# Sheet2.net
KiCad netlist of a schematic drawn in Altium Designer
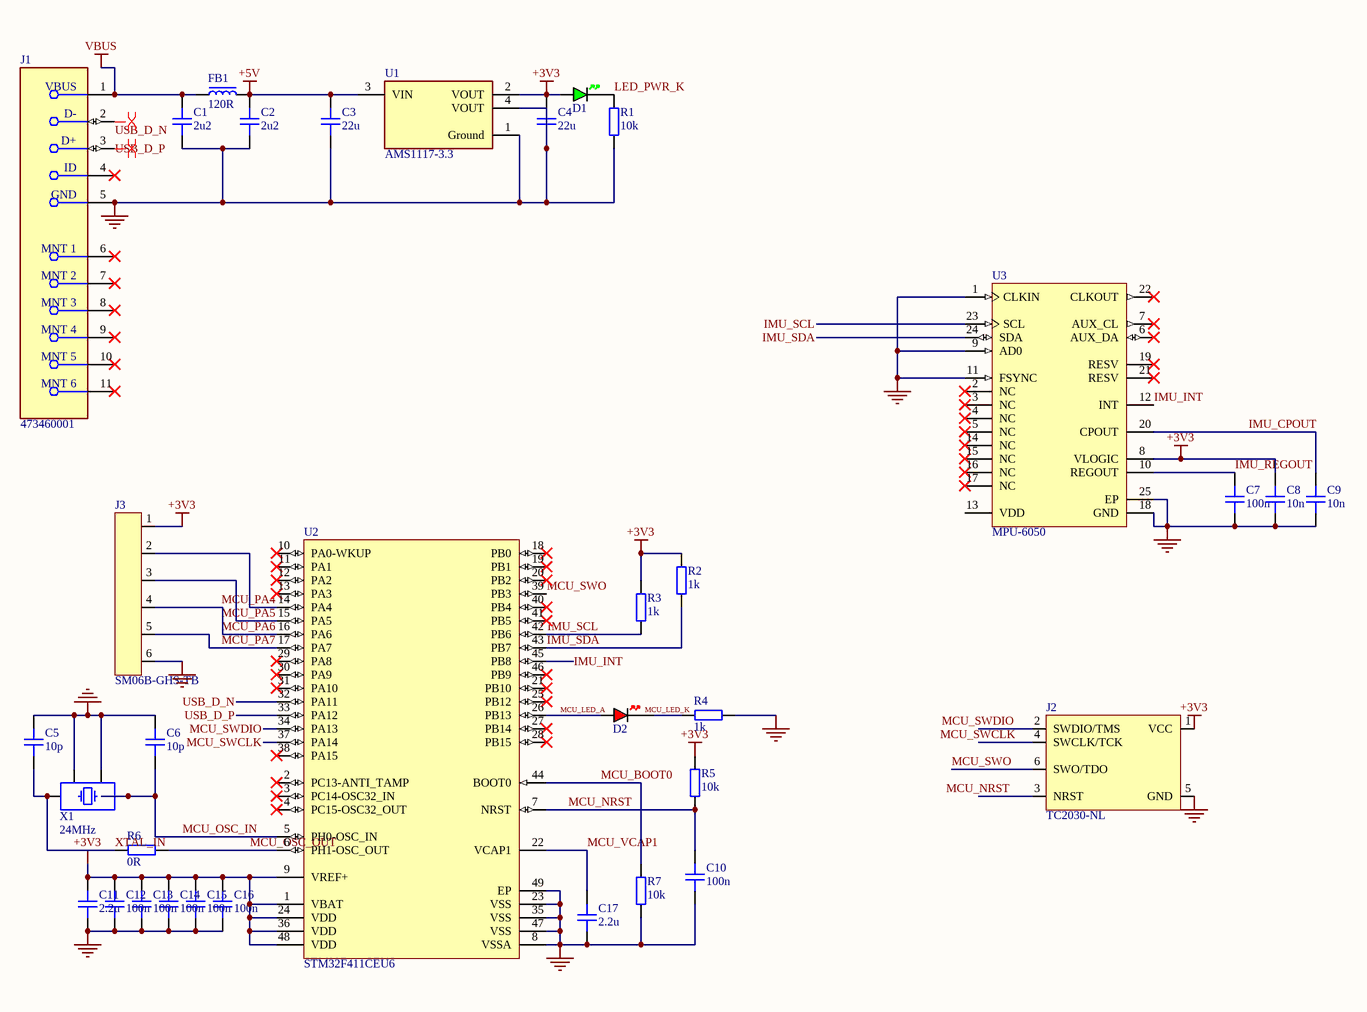
[diagram p0: Sheet2.SchDoc]

(export (version "E")
  (design (tool "Eeschema 10.0.6"))
  (components
    (comp (ref "C1")
      (value "2u2")
      (footprint "CAP_0402")
      (description "Capacitor SMD 0402")
      (libsource (lib "Schematic-Lib-PhilsLab") (part "CAP_0402"))
    )
    (comp (ref "C2")
      (value "2u2")
      (footprint "CAP_0402")
      (description "Capacitor SMD 0402")
      (libsource (lib "Schematic-Lib-PhilsLab") (part "CAP_0402"))
    )
    (comp (ref "C3")
      (value "22u")
      (footprint "CAP_0805")
      (description "Capacitor SMD 0805")
      (libsource (lib "Schematic-Lib-PhilsLab") (part "CAP_0805"))
    )
    (comp (ref "C4")
      (value "22u")
      (footprint "CAP_0805")
      (description "Capacitor SMD 0805")
      (libsource (lib "Schematic-Lib-PhilsLab") (part "CAP_0805"))
    )
    (comp (ref "C5")
      (value "10p")
      (footprint "CAP_0402")
      (description "Capacitor SMD 0402")
      (libsource (lib "Schematic-Lib-PhilsLab") (part "CAP_0402"))
    )
    (comp (ref "C6")
      (value "10p")
      (footprint "CAP_0402")
      (description "Capacitor SMD 0402")
      (libsource (lib "Schematic-Lib-PhilsLab") (part "CAP_0402"))
    )
    (comp (ref "C7")
      (value "100n")
      (footprint "CAP_0402")
      (description "Capacitor SMD 0402")
      (libsource (lib "Schematic-Lib-PhilsLab") (part "CAP_0402"))
    )
    (comp (ref "C8")
      (value "10n")
      (footprint "CAP_0402")
      (description "Capacitor SMD 0402")
      (libsource (lib "Schematic-Lib-PhilsLab") (part "CAP_0402"))
    )
    (comp (ref "C9")
      (value "10n")
      (footprint "CAP_0402")
      (description "Capacitor SMD 0402")
      (libsource (lib "Schematic-Lib-PhilsLab") (part "CAP_0402"))
    )
    (comp (ref "C10")
      (value "100n")
      (footprint "CAP_0402")
      (description "Capacitor SMD 0402")
      (libsource (lib "Schematic-Lib-PhilsLab") (part "CAP_0402"))
    )
    (comp (ref "C11")
      (value "2.2u")
      (footprint "CAP_0603")
      (description "Capacitor SMD 0603")
      (libsource (lib "Schematic-Lib-PhilsLab") (part "CAP_0603"))
    )
    (comp (ref "C12")
      (value "100n")
      (footprint "CAP_0402")
      (description "Capacitor SMD 0402")
      (libsource (lib "Schematic-Lib-PhilsLab") (part "CAP_0402"))
    )
    (comp (ref "C13")
      (value "100n")
      (footprint "CAP_0402")
      (description "Capacitor SMD 0402")
      (libsource (lib "Schematic-Lib-PhilsLab") (part "CAP_0402"))
    )
    (comp (ref "C14")
      (value "100n")
      (footprint "CAP_0402")
      (description "Capacitor SMD 0402")
      (libsource (lib "Schematic-Lib-PhilsLab") (part "CAP_0402"))
    )
    (comp (ref "C15")
      (value "100n")
      (footprint "CAP_0402")
      (description "Capacitor SMD 0402")
      (libsource (lib "Schematic-Lib-PhilsLab") (part "CAP_0402"))
    )
    (comp (ref "C16")
      (value "100n")
      (footprint "CAP_0402")
      (description "Capacitor SMD 0402")
      (libsource (lib "Schematic-Lib-PhilsLab") (part "CAP_0402"))
    )
    (comp (ref "C17")
      (value "2.2u")
      (footprint "CAP_0603")
      (description "Capacitor SMD 0603")
      (libsource (lib "Schematic-Lib-PhilsLab") (part "CAP_0603"))
    )
    (comp (ref "D1")
      (value "GREEN")
      (footprint "LED_0402_GREEN")
      (description "LED 0402 GREEN SMD")
      (libsource (lib "Schematic-Lib-PhilsLab") (part "LED_0402_GREEN"))
    )
    (comp (ref "D2")
      (value "RED")
      (footprint "LED_0402_RED")
      (description "LED 0402 RED SMD")
      (libsource (lib "Schematic-Lib-PhilsLab") (part "LED_0402_RED"))
    )
    (comp (ref "FB1")
      (value "120R")
      (footprint "FB_0603")
      (description "Ferrite Bead SMD 0603")
      (libsource (lib "Schematic-Lib-PhilsLab") (part "FB_0603"))
    )
    (comp (ref "J1")
      (value "473460001")
      (footprint "FP-473460001-MFG")
      (description "USB - micro B USB 2.0 Receptacle Connector 5 Position Surface Mount, Right Angle")
      (fields (field (name "OCTOPART") "https://octopart.com/47346-0001-molex-7164928"))
      (libsource (lib "Altium Content Vault") (part "53ae1f1d9b557310b43ca686e5bb76a"))
    )
    (comp (ref "J2")
      (value "TC2030-NL")
      (footprint "TC2030-NL-FP")
      (description "Tag-Connect No-Solder SWD Debug Connector (No Legs) DO NOT PLACE")
      (fields
        (field (name "MANUFACTURER") "Tag-Connect")
        (field (name "MANUFACTURER PART NUMBER") "TC2030-NL-FP")
      )
      (libsource (lib "Schematic-Lib-PhilsLab") (part "TC2030-NL"))
    )
    (comp (ref "J3")
      (value "SM06B-GHS-TB")
      (footprint "SM06B-GHS-TB")
      (description "Header Connector 6 Position 1.25MM Pitch SMD Horizontal JST GH")
      (fields (field (name "MANUFACTURER") "JST"))
      (libsource (lib "Schematic-Lib-PhilsLab") (part "SM06B-GHS-TB"))
    )
    (comp (ref "R1")
      (value "10k")
      (footprint "RES_0402")
      (description "Resistor SMD 0402")
      (libsource (lib "Schematic-Lib-PhilsLab") (part "RES_0402"))
    )
    (comp (ref "R2")
      (value "1k")
      (footprint "RES_0402")
      (description "Resistor SMD 0402")
      (libsource (lib "Schematic-Lib-PhilsLab") (part "RES_0402"))
    )
    (comp (ref "R3")
      (value "1k")
      (footprint "RES_0402")
      (description "Resistor SMD 0402")
      (libsource (lib "Schematic-Lib-PhilsLab") (part "RES_0402"))
    )
    (comp (ref "R4")
      (value "1k")
      (footprint "RES_0402")
      (description "Resistor SMD 0402")
      (libsource (lib "Schematic-Lib-PhilsLab") (part "RES_0402"))
    )
    (comp (ref "R5")
      (value "10k")
      (footprint "RES_0402")
      (description "Resistor SMD 0402")
      (libsource (lib "Schematic-Lib-PhilsLab") (part "RES_0402"))
    )
    (comp (ref "R6")
      (value "0R")
      (footprint "RES_0402")
      (description "Resistor SMD 0402")
      (libsource (lib "Schematic-Lib-PhilsLab") (part "RES_0402"))
    )
    (comp (ref "R7")
      (value "10k")
      (footprint "RES_0402")
      (description "Resistor SMD 0402")
      (libsource (lib "Schematic-Lib-PhilsLab") (part "RES_0402"))
    )
    (comp (ref "U1")
      (value "AMS1117-3.3")
      (footprint "FP-AMS1117-IPC_C")
      (description "LDO Voltage Regulators 1A, 3.3V")
      (fields
        (field (name "OCTOPART") "https://octopart.com/ams1117-3.3-advanced+monolithic+systems-25899300")
        (field (name "MANUFACTURER") "Advanced Monolithic Systems")
      )
      (libsource (lib "Altium Content Vault") (part "8bdbb5f8e77002000e30dd2845d0354"))
    )
    (comp (ref "U2")
      (value "STM32F411CEU6")
      (footprint "STM-UFQFPN48_L")
      (libsource (lib "Altium Content Vault") (part "MC-ARM-STM32F411-UFQFPN48"))
    )
    (comp (ref "U3")
      (value "MPU-6050")
      (footprint "IS-QFN-24_V")
      (fields (field (name "MANUFACTURER") "InvenSense"))
      (libsource (lib "Altium Content Vault") (part "IS-MPU-6050-QFN-24"))
    )
    (comp (ref "X1")
      (value "24MHz")
      (footprint "XTAL_3225")
      (description "Crystal SMD 24MHz 10PPM 7pF 3225")
      (fields
        (field (name "MANUFACTURER") "Epson")
        (field (name "MANUFACTURER PART NUMBER") "TSX-3225 24.0000MF15X-AC")
      )
      (libsource (lib "Schematic-Lib-PhilsLab") (part "TSX-3225_24.0000MF15X-AC"))
    )
  )
  (nets
    (net (code "1") (name "+3V3") (class "Default")
      (node (ref "C11") (pin "2") (pinfunction "2_2") (pintype "passive"))
      (node (ref "C12") (pin "2") (pinfunction "2_2") (pintype "passive"))
      (node (ref "C13") (pin "2") (pinfunction "2_2") (pintype "passive"))
      (node (ref "C14") (pin "2") (pinfunction "2_2") (pintype "passive"))
      (node (ref "C15") (pin "2") (pinfunction "2_2") (pintype "passive"))
      (node (ref "C16") (pin "2") (pinfunction "2_2") (pintype "passive"))
      (node (ref "C4") (pin "2") (pinfunction "2_2") (pintype "passive"))
      (node (ref "C8") (pin "2") (pinfunction "2_2") (pintype "passive"))
      (node (ref "D1") (pin "A") (pinfunction "A_A") (pintype "passive"))
      (node (ref "J2") (pin "1") (pinfunction "VCC_1") (pintype "passive"))
      (node (ref "J3") (pin "1") (pinfunction "1_1") (pintype "passive"))
      (node (ref "R2") (pin "1") (pinfunction "1_1") (pintype "passive"))
      (node (ref "R3") (pin "1") (pinfunction "1_1") (pintype "passive"))
      (node (ref "R5") (pin "2") (pinfunction "2_2") (pintype "passive"))
      (node (ref "U1") (pin "2") (pinfunction "VOUT_2") (pintype "passive"))
      (node (ref "U2") (pin "1") (pinfunction "VBAT_1") (pintype "power_in"))
      (node (ref "U2") (pin "24") (pinfunction "VDD_24") (pintype "power_in"))
      (node (ref "U2") (pin "36") (pinfunction "VDD_36") (pintype "power_in"))
      (node (ref "U2") (pin "48") (pinfunction "VDD_48") (pintype "power_in"))
      (node (ref "U2") (pin "9") (pinfunction "VREF+_9") (pintype "power_in"))
      (node (ref "U3") (pin "8") (pinfunction "VLOGIC_8") (pintype "power_in"))
    )
    (net (code "2") (name "+5V") (class "Default")
      (node (ref "C2") (pin "2") (pinfunction "2_2") (pintype "passive"))
      (node (ref "C3") (pin "2") (pinfunction "2_2") (pintype "passive"))
      (node (ref "FB1") (pin "2") (pinfunction "2_2") (pintype "passive"))
      (node (ref "U1") (pin "3") (pinfunction "VIN_3") (pintype "power_in"))
    )
    (net (code "3") (name "/IMU_CPOUT") (class "Default")
      (node (ref "C9") (pin "2") (pinfunction "2_2") (pintype "passive"))
      (node (ref "U3") (pin "20") (pinfunction "CPOUT_20") (pintype "passive"))
    )
    (net (code "4") (name "/IMU_INT") (class "Default")
      (node (ref "U2") (pin "45") (pinfunction "PB8_45") (pintype "bidirectional"))
      (node (ref "U3") (pin "12") (pinfunction "INT_12") (pintype "open_collector"))
    )
    (net (code "5") (name "/IMU_REGOUT") (class "Default")
      (node (ref "C7") (pin "2") (pinfunction "2_2") (pintype "passive"))
      (node (ref "U3") (pin "10") (pinfunction "REGOUT_10") (pintype "passive"))
    )
    (net (code "6") (name "/IMU_SCL") (class "Default")
      (node (ref "R3") (pin "2") (pinfunction "2_2") (pintype "passive"))
      (node (ref "U2") (pin "42") (pinfunction "PB6_42") (pintype "bidirectional"))
      (node (ref "U3") (pin "23") (pinfunction "SCL_23") (pintype "input"))
    )
    (net (code "7") (name "/IMU_SDA") (class "Default")
      (node (ref "R2") (pin "2") (pinfunction "2_2") (pintype "passive"))
      (node (ref "U2") (pin "43") (pinfunction "PB7_43") (pintype "bidirectional"))
      (node (ref "U3") (pin "24") (pinfunction "SDA_24") (pintype "bidirectional"))
    )
    (net (code "8") (name "/LED_PWR_K") (class "Default")
      (node (ref "D1") (pin "K") (pinfunction "K_K") (pintype "passive"))
      (node (ref "R1") (pin "2") (pinfunction "2_2") (pintype "passive"))
    )
    (net (code "9") (name "/MCU_BOOT0") (class "Default")
      (node (ref "R7") (pin "2") (pinfunction "2_2") (pintype "passive"))
      (node (ref "U2") (pin "44") (pinfunction "BOOT0_44") (pintype "input"))
    )
    (net (code "10") (name "/MCU_LED_A") (class "Default")
      (node (ref "D2") (pin "A") (pinfunction "A_A") (pintype "passive"))
      (node (ref "U2") (pin "26") (pinfunction "PB13_26") (pintype "bidirectional"))
    )
    (net (code "11") (name "/MCU_LED_K") (class "Default")
      (node (ref "D2") (pin "K") (pinfunction "K_K") (pintype "passive"))
      (node (ref "R4") (pin "2") (pinfunction "2_2") (pintype "passive"))
    )
    (net (code "12") (name "/MCU_NRST") (class "Default")
      (node (ref "C10") (pin "2") (pinfunction "2_2") (pintype "passive"))
      (node (ref "J2") (pin "3") (pinfunction "NRST_3") (pintype "passive"))
      (node (ref "R5") (pin "1") (pinfunction "1_1") (pintype "passive"))
      (node (ref "U2") (pin "7") (pinfunction "NRST_7") (pintype "bidirectional"))
    )
    (net (code "13") (name "/MCU_OSC_IN") (class "Default")
      (node (ref "C6") (pin "1") (pinfunction "1_1") (pintype "passive"))
      (node (ref "U2") (pin "5") (pinfunction "PH0-OSC_IN_5") (pintype "bidirectional"))
      (node (ref "X1") (pin "1") (pinfunction "1_1") (pintype "passive"))
    )
    (net (code "14") (name "/MCU_OSC_OUT") (class "Default")
      (node (ref "R6") (pin "1") (pinfunction "1_1") (pintype "passive"))
      (node (ref "U2") (pin "6") (pinfunction "PH1-OSC_OUT_6") (pintype "bidirectional"))
    )
    (net (code "15") (name "/MCU_PA4") (class "Default")
      (node (ref "J3") (pin "2") (pinfunction "2_2") (pintype "passive"))
      (node (ref "U2") (pin "14") (pinfunction "PA4_14") (pintype "bidirectional"))
    )
    (net (code "16") (name "/MCU_PA5") (class "Default")
      (node (ref "J3") (pin "3") (pinfunction "3_3") (pintype "passive"))
      (node (ref "U2") (pin "15") (pinfunction "PA5_15") (pintype "bidirectional"))
    )
    (net (code "17") (name "/MCU_PA6") (class "Default")
      (node (ref "J3") (pin "4") (pinfunction "4_4") (pintype "passive"))
      (node (ref "U2") (pin "16") (pinfunction "PA6_16") (pintype "bidirectional"))
    )
    (net (code "18") (name "/MCU_PA7") (class "Default")
      (node (ref "J3") (pin "5") (pinfunction "5_5") (pintype "passive"))
      (node (ref "U2") (pin "17") (pinfunction "PA7_17") (pintype "bidirectional"))
    )
    (net (code "19") (name "/MCU_SWCLK") (class "Default")
      (node (ref "J2") (pin "4") (pinfunction "SWCLK/TCK_4") (pintype "passive"))
      (node (ref "U2") (pin "37") (pinfunction "PA14_37") (pintype "bidirectional"))
    )
    (net (code "20") (name "/MCU_SWDIO") (class "Default")
      (node (ref "J2") (pin "2") (pinfunction "SWDIO/TMS_2") (pintype "passive"))
      (node (ref "U2") (pin "34") (pinfunction "PA13_34") (pintype "bidirectional"))
    )
    (net (code "21") (name "/MCU_SWO") (class "Default")
      (node (ref "J2") (pin "6") (pinfunction "SWO/TDO_6") (pintype "passive"))
      (node (ref "U2") (pin "39") (pinfunction "PB3_39") (pintype "bidirectional"))
    )
    (net (code "22") (name "/MCU_VCAP1") (class "Default")
      (node (ref "C17") (pin "2") (pinfunction "2_2") (pintype "passive"))
      (node (ref "U2") (pin "22") (pinfunction "VCAP1_22") (pintype "passive"))
    )
    (net (code "23") (name "/USB_D_N") (class "Default")
      (node (ref "J1") (pin "2") (pinfunction "D-_2") (pintype "bidirectional"))
      (node (ref "U2") (pin "32") (pinfunction "PA11_32") (pintype "bidirectional"))
    )
    (net (code "24") (name "/USB_D_P") (class "Default")
      (node (ref "J1") (pin "3") (pinfunction "D+_3") (pintype "bidirectional"))
      (node (ref "U2") (pin "33") (pinfunction "PA12_33") (pintype "bidirectional"))
    )
    (net (code "25") (name "/XTAL_IN") (class "Default")
      (node (ref "C5") (pin "1") (pinfunction "1_1") (pintype "passive"))
      (node (ref "R6") (pin "2") (pinfunction "2_2") (pintype "passive"))
      (node (ref "X1") (pin "3") (pinfunction "3_3") (pintype "passive"))
    )
    (net (code "26") (name "GND") (class "Default")
      (node (ref "C1") (pin "1") (pinfunction "1_1") (pintype "passive"))
      (node (ref "C10") (pin "1") (pinfunction "1_1") (pintype "passive"))
      (node (ref "C11") (pin "1") (pinfunction "1_1") (pintype "passive"))
      (node (ref "C12") (pin "1") (pinfunction "1_1") (pintype "passive"))
      (node (ref "C13") (pin "1") (pinfunction "1_1") (pintype "passive"))
      (node (ref "C14") (pin "1") (pinfunction "1_1") (pintype "passive"))
      (node (ref "C15") (pin "1") (pinfunction "1_1") (pintype "passive"))
      (node (ref "C16") (pin "1") (pinfunction "1_1") (pintype "passive"))
      (node (ref "C17") (pin "1") (pinfunction "1_1") (pintype "passive"))
      (node (ref "C2") (pin "1") (pinfunction "1_1") (pintype "passive"))
      (node (ref "C3") (pin "1") (pinfunction "1_1") (pintype "passive"))
      (node (ref "C4") (pin "1") (pinfunction "1_1") (pintype "passive"))
      (node (ref "C5") (pin "2") (pinfunction "2_2") (pintype "passive"))
      (node (ref "C6") (pin "2") (pinfunction "2_2") (pintype "passive"))
      (node (ref "C7") (pin "1") (pinfunction "1_1") (pintype "passive"))
      (node (ref "C8") (pin "1") (pinfunction "1_1") (pintype "passive"))
      (node (ref "C9") (pin "1") (pinfunction "1_1") (pintype "passive"))
      (node (ref "J1") (pin "5") (pinfunction "GND_5") (pintype "power_in"))
      (node (ref "J2") (pin "5") (pinfunction "GND_5") (pintype "passive"))
      (node (ref "J3") (pin "6") (pinfunction "6_6") (pintype "passive"))
      (node (ref "R1") (pin "1") (pinfunction "1_1") (pintype "passive"))
      (node (ref "R4") (pin "1") (pinfunction "1_1") (pintype "passive"))
      (node (ref "R7") (pin "1") (pinfunction "1_1") (pintype "passive"))
      (node (ref "U1") (pin "1") (pinfunction "Ground_1") (pintype "power_in"))
      (node (ref "U1") (pin "4") (pinfunction "VOUT_4") (pintype "passive"))
      (node (ref "U2") (pin "23") (pinfunction "VSS_23") (pintype "power_in"))
      (node (ref "U2") (pin "35") (pinfunction "VSS_35") (pintype "power_in"))
      (node (ref "U2") (pin "47") (pinfunction "VSS_47") (pintype "power_in"))
      (node (ref "U2") (pin "49") (pinfunction "EP_49") (pintype "power_in"))
      (node (ref "U2") (pin "8") (pinfunction "VSSA_8") (pintype "power_in"))
      (node (ref "U3") (pin "1") (pinfunction "CLKIN_1") (pintype "input"))
      (node (ref "U3") (pin "11") (pinfunction "FSYNC_11") (pintype "input"))
      (node (ref "U3") (pin "18") (pinfunction "GND_18") (pintype "power_in"))
      (node (ref "U3") (pin "25") (pinfunction "EP_25") (pintype "power_in"))
      (node (ref "U3") (pin "9") (pinfunction "AD0_9") (pintype "input"))
      (node (ref "X1") (pin "2") (pinfunction "2_2") (pintype "passive"))
      (node (ref "X1") (pin "4") (pinfunction "4_4") (pintype "passive"))
    )
    (net (code "27") (name "VBUS") (class "Default")
      (node (ref "C1") (pin "2") (pinfunction "2_2") (pintype "passive"))
      (node (ref "FB1") (pin "1") (pinfunction "1_1") (pintype "passive"))
      (node (ref "J1") (pin "1") (pinfunction "VBUS_1") (pintype "power_in"))
    )
    (net (code "28") (name "unconnected-(J1-ID-Pad4)") (class "Default")
      (node (ref "J1") (pin "4") (pinfunction "ID_4") (pintype "passive+no_connect"))
    )
    (net (code "29") (name "unconnected-(J1-MNT_1-Pad6)") (class "Default")
      (node (ref "J1") (pin "6") (pinfunction "MNT_1_6") (pintype "passive+no_connect"))
    )
    (net (code "30") (name "unconnected-(J1-MNT_2-Pad7)") (class "Default")
      (node (ref "J1") (pin "7") (pinfunction "MNT_2_7") (pintype "passive+no_connect"))
    )
    (net (code "31") (name "unconnected-(J1-MNT_3-Pad8)") (class "Default")
      (node (ref "J1") (pin "8") (pinfunction "MNT_3_8") (pintype "passive+no_connect"))
    )
    (net (code "32") (name "unconnected-(J1-MNT_4-Pad9)") (class "Default")
      (node (ref "J1") (pin "9") (pinfunction "MNT_4_9") (pintype "passive+no_connect"))
    )
    (net (code "33") (name "unconnected-(J1-MNT_5-Pad10)") (class "Default")
      (node (ref "J1") (pin "10") (pinfunction "MNT_5_10") (pintype "passive+no_connect"))
    )
    (net (code "34") (name "unconnected-(J1-MNT_6-Pad11)") (class "Default")
      (node (ref "J1") (pin "11") (pinfunction "MNT_6_11") (pintype "passive+no_connect"))
    )
    (net (code "35") (name "unconnected-(U2-PA0-WKUP-Pad10)") (class "Default")
      (node (ref "U2") (pin "10") (pinfunction "PA0-WKUP_10") (pintype "bidirectional+no_connect"))
    )
    (net (code "36") (name "unconnected-(U2-PA1-Pad11)") (class "Default")
      (node (ref "U2") (pin "11") (pinfunction "PA1_11") (pintype "bidirectional+no_connect"))
    )
    (net (code "37") (name "unconnected-(U2-PA2-Pad12)") (class "Default")
      (node (ref "U2") (pin "12") (pinfunction "PA2_12") (pintype "bidirectional+no_connect"))
    )
    (net (code "38") (name "unconnected-(U2-PA3-Pad13)") (class "Default")
      (node (ref "U2") (pin "13") (pinfunction "PA3_13") (pintype "bidirectional+no_connect"))
    )
    (net (code "39") (name "unconnected-(U2-PA8-Pad29)") (class "Default")
      (node (ref "U2") (pin "29") (pinfunction "PA8_29") (pintype "bidirectional+no_connect"))
    )
    (net (code "40") (name "unconnected-(U2-PA9-Pad30)") (class "Default")
      (node (ref "U2") (pin "30") (pinfunction "PA9_30") (pintype "bidirectional+no_connect"))
    )
    (net (code "41") (name "unconnected-(U2-PA10-Pad31)") (class "Default")
      (node (ref "U2") (pin "31") (pinfunction "PA10_31") (pintype "bidirectional+no_connect"))
    )
    (net (code "42") (name "unconnected-(U2-PA15-Pad38)") (class "Default")
      (node (ref "U2") (pin "38") (pinfunction "PA15_38") (pintype "bidirectional+no_connect"))
    )
    (net (code "43") (name "unconnected-(U2-PB0-Pad18)") (class "Default")
      (node (ref "U2") (pin "18") (pinfunction "PB0_18") (pintype "bidirectional+no_connect"))
    )
    (net (code "44") (name "unconnected-(U2-PB1-Pad19)") (class "Default")
      (node (ref "U2") (pin "19") (pinfunction "PB1_19") (pintype "bidirectional+no_connect"))
    )
    (net (code "45") (name "unconnected-(U2-PB2-Pad20)") (class "Default")
      (node (ref "U2") (pin "20") (pinfunction "PB2_20") (pintype "bidirectional+no_connect"))
    )
    (net (code "46") (name "unconnected-(U2-PB4-Pad40)") (class "Default")
      (node (ref "U2") (pin "40") (pinfunction "PB4_40") (pintype "bidirectional+no_connect"))
    )
    (net (code "47") (name "unconnected-(U2-PB5-Pad41)") (class "Default")
      (node (ref "U2") (pin "41") (pinfunction "PB5_41") (pintype "bidirectional+no_connect"))
    )
    (net (code "48") (name "unconnected-(U2-PB9-Pad46)") (class "Default")
      (node (ref "U2") (pin "46") (pinfunction "PB9_46") (pintype "bidirectional+no_connect"))
    )
    (net (code "49") (name "unconnected-(U2-PB10-Pad21)") (class "Default")
      (node (ref "U2") (pin "21") (pinfunction "PB10_21") (pintype "bidirectional+no_connect"))
    )
    (net (code "50") (name "unconnected-(U2-PB12-Pad25)") (class "Default")
      (node (ref "U2") (pin "25") (pinfunction "PB12_25") (pintype "bidirectional+no_connect"))
    )
    (net (code "51") (name "unconnected-(U2-PB14-Pad27)") (class "Default")
      (node (ref "U2") (pin "27") (pinfunction "PB14_27") (pintype "bidirectional+no_connect"))
    )
    (net (code "52") (name "unconnected-(U2-PB15-Pad28)") (class "Default")
      (node (ref "U2") (pin "28") (pinfunction "PB15_28") (pintype "bidirectional+no_connect"))
    )
    (net (code "53") (name "unconnected-(U2-PC13-ANTI_TAMP-Pad2)") (class "Default")
      (node (ref "U2") (pin "2") (pinfunction "PC13-ANTI_TAMP_2") (pintype "bidirectional+no_connect"))
    )
    (net (code "54") (name "unconnected-(U2-PC14-OSC32_IN-Pad3)") (class "Default")
      (node (ref "U2") (pin "3") (pinfunction "PC14-OSC32_IN_3") (pintype "bidirectional+no_connect"))
    )
    (net (code "55") (name "unconnected-(U2-PC15-OSC32_OUT-Pad4)") (class "Default")
      (node (ref "U2") (pin "4") (pinfunction "PC15-OSC32_OUT_4") (pintype "bidirectional+no_connect"))
    )
    (net (code "56") (name "unconnected-(U3-AUX_CL-Pad7)") (class "Default")
      (node (ref "U3") (pin "7") (pinfunction "AUX_CL_7") (pintype "output+no_connect"))
    )
    (net (code "57") (name "unconnected-(U3-AUX_DA-Pad6)") (class "Default")
      (node (ref "U3") (pin "6") (pinfunction "AUX_DA_6") (pintype "bidirectional+no_connect"))
    )
    (net (code "58") (name "unconnected-(U3-CLKOUT-Pad22)") (class "Default")
      (node (ref "U3") (pin "22") (pinfunction "CLKOUT_22") (pintype "output+no_connect"))
    )
    (net (code "59") (name "unconnected-(U3-NC-Pad2)") (class "Default")
      (node (ref "U3") (pin "2") (pinfunction "NC_2") (pintype "passive+no_connect"))
    )
    (net (code "60") (name "unconnected-(U3-NC-Pad3)") (class "Default")
      (node (ref "U3") (pin "3") (pinfunction "NC_3") (pintype "passive+no_connect"))
    )
    (net (code "61") (name "unconnected-(U3-NC-Pad4)") (class "Default")
      (node (ref "U3") (pin "4") (pinfunction "NC_4") (pintype "passive+no_connect"))
    )
    (net (code "62") (name "unconnected-(U3-NC-Pad5)") (class "Default")
      (node (ref "U3") (pin "5") (pinfunction "NC_5") (pintype "passive+no_connect"))
    )
    (net (code "63") (name "unconnected-(U3-NC-Pad14)") (class "Default")
      (node (ref "U3") (pin "14") (pinfunction "NC_14") (pintype "passive+no_connect"))
    )
    (net (code "64") (name "unconnected-(U3-NC-Pad15)") (class "Default")
      (node (ref "U3") (pin "15") (pinfunction "NC_15") (pintype "passive+no_connect"))
    )
    (net (code "65") (name "unconnected-(U3-NC-Pad16)") (class "Default")
      (node (ref "U3") (pin "16") (pinfunction "NC_16") (pintype "passive+no_connect"))
    )
    (net (code "66") (name "unconnected-(U3-NC-Pad17)") (class "Default")
      (node (ref "U3") (pin "17") (pinfunction "NC_17") (pintype "passive+no_connect"))
    )
    (net (code "67") (name "unconnected-(U3-RESV-Pad19)") (class "Default")
      (node (ref "U3") (pin "19") (pinfunction "RESV_19") (pintype "passive+no_connect"))
    )
    (net (code "68") (name "unconnected-(U3-RESV-Pad21)") (class "Default")
      (node (ref "U3") (pin "21") (pinfunction "RESV_21") (pintype "passive+no_connect"))
    )
    (net (code "69") (name "unconnected-(U3-VDD-Pad13)") (class "Default")
      (node (ref "U3") (pin "13") (pinfunction "VDD_13") (pintype "power_in"))
    )
  )
)
